# SCH_power_supply_2023-04-18.net
KiCad netlist of a schematic drawn in EasyEDA
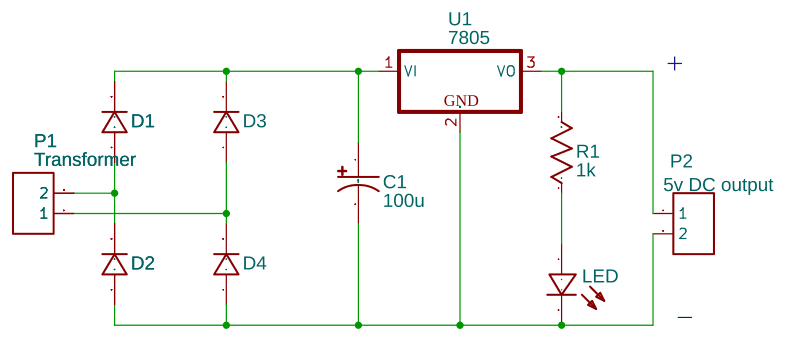
[diagram p0: schematic sheet]

(export (version "E")
  (design (tool "Eeschema 10.0.6"))
  (components
    (comp (ref "C1")
      (value "100u")
      (fields (field (name "BOM_Manufacturer Part") "?"))
      (libsource (lib "") (part "Cap_Electrolytic(TH)_D3.0XF1.5_US"))
    )
    (comp (ref "D1")
      (value "1N4448")
      (fields (field (name "BOM_Supplier Part") "C54037"))
      (libsource (lib "") (part "Unknown_785_550"))
    )
    (comp (ref "D2")
      (value "1N4448")
      (fields (field (name "BOM_Supplier Part") "C54037"))
      (libsource (lib "") (part "Unknown_785_620"))
    )
    (comp (ref "D3")
      (value "1N4448")
      (fields (field (name "BOM_Supplier Part") "C54037"))
      (libsource (lib "") (part "Unknown_840_550"))
    )
    (comp (ref "D4")
      (value "1N4448")
      (fields (field (name "BOM_Supplier Part") "C54037"))
      (libsource (lib "") (part "Unknown_840_620"))
    )
    (comp (ref "LED")
      (value "LED-3MM")
      (fields
        (field (name "BOM_Manufacturer Part") "204-10SURD/S530-A3")
        (field (name "BOM_Supplier Part") "C99772")
      )
      (libsource (lib "") (part "Unknown_1005_630"))
    )
    (comp (ref "P1")
      (value "Transformer")
      (fields
        (field (name "BOM_Manufacturer Part") "2.54-1*2PFemale")
        (field (name "BOM_Supplier Part") "C49661")
      )
      (libsource (lib "") (part "Unknown_750_590"))
    )
    (comp (ref "P2")
      (value "5v DC output")
      (fields
        (field (name "BOM_Manufacturer Part") "2.54-1*2PFemale")
        (field (name "BOM_Supplier Part") "C49661")
      )
      (libsource (lib "") (part "Unknown_1065_600"))
    )
    (comp (ref "R1")
      (value "1k")
      (fields (field (name "BOM_Manufacturer Part") "?"))
      (libsource (lib "") (part "Res_AXIAL-0.3(1/8W)_US"))
    )
    (comp (ref "U1")
      (value "7805")
      (fields (field (name "BOM_Manufacturer Part") "?"))
      (libsource (lib "") (part "Unknown_955_525"))
    )
  )
  (nets
    (net (code "1") (name "Net-(D1-A)") (class "Default")
      (node (ref "D1") (pin "1") (pinfunction "A_1") (pintype "unspecified"))
      (node (ref "D2") (pin "2") (pinfunction "K_2") (pintype "unspecified"))
      (node (ref "P1") (pin "2") (pinfunction "2_2") (pintype "input"))
    )
    (net (code "2") (name "Net-(D1-K)") (class "Default")
      (node (ref "C1") (pin "1") (pinfunction "1_1") (pintype "unspecified"))
      (node (ref "D1") (pin "2") (pinfunction "K_2") (pintype "unspecified"))
      (node (ref "D3") (pin "2") (pinfunction "K_2") (pintype "unspecified"))
      (node (ref "U1") (pin "1") (pinfunction "VI_1") (pintype "input"))
    )
    (net (code "3") (name "Net-(D2-A)") (class "Default")
      (node (ref "C1") (pin "2") (pinfunction "2_2") (pintype "unspecified"))
      (node (ref "D2") (pin "1") (pinfunction "A_1") (pintype "unspecified"))
      (node (ref "D4") (pin "1") (pinfunction "A_1") (pintype "unspecified"))
      (node (ref "LED") (pin "2") (pinfunction "-_2") (pintype "unspecified"))
      (node (ref "P2") (pin "2") (pinfunction "2_2") (pintype "input"))
      (node (ref "U1") (pin "2") (pinfunction "GND_2") (pintype "unspecified"))
    )
    (net (code "4") (name "Net-(D3-A)") (class "Default")
      (node (ref "D3") (pin "1") (pinfunction "A_1") (pintype "unspecified"))
      (node (ref "D4") (pin "2") (pinfunction "K_2") (pintype "unspecified"))
      (node (ref "P1") (pin "1") (pinfunction "1_1") (pintype "input"))
    )
    (net (code "5") (name "Net-(LED-+)") (class "Default")
      (node (ref "LED") (pin "1") (pinfunction "+_1") (pintype "unspecified"))
      (node (ref "R1") (pin "1") (pinfunction "1_1") (pintype "unspecified"))
    )
    (net (code "6") (name "Net-(U1-VO)") (class "Default")
      (node (ref "P2") (pin "1") (pinfunction "1_1") (pintype "input"))
      (node (ref "R1") (pin "2") (pinfunction "2_2") (pintype "unspecified"))
      (node (ref "U1") (pin "3") (pinfunction "VO_3") (pintype "unspecified"))
    )
  )
)
